# design.net
KiCad netlist of a schematic drawn in Altium Designer
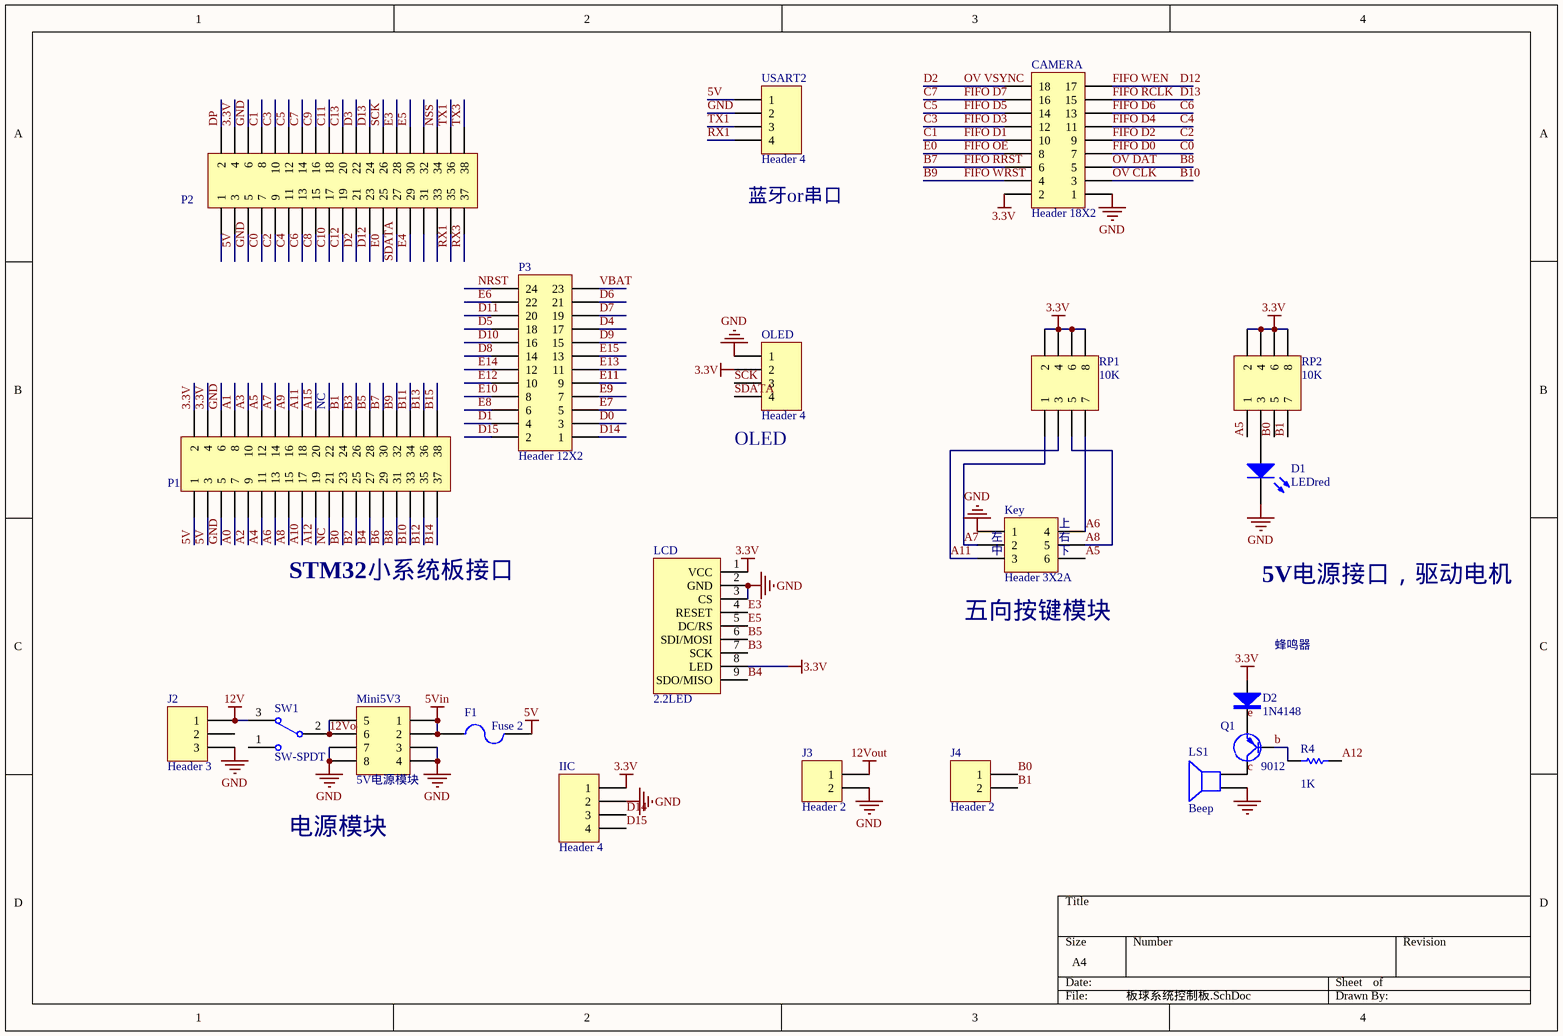
[diagram p0: 板球系统控制板.SchDoc]

(export (version "E")
  (design (tool "Eeschema 10.0.6"))
  (components
    (comp (ref "CAMERA")
      (value "Header 18X2")
      (footprint "HDR2X9H")
      (description "Header, 9-Pin, Dual row")
      (fields (field (name "PUBLISHER") "Altium Limited"))
      (libsource (lib "Miscellaneous Connectors") (part "Header 9X2"))
    )
    (comp (ref "D1")
      (value "LEDred")
      (footprint "0805_LED_S4")
      (description "Typical INFRARED GaAs LED")
      (fields (field (name "PUBLISHER") "Altium Limited"))
      (libsource (lib "Miscellaneous Devices") (part "LED0"))
    )
    (comp (ref "D2")
      (value "1N4148")
      (footprint "SOD-123")
      (description "Diode")
      (libsource (lib "*") (part "1N4148"))
    )
    (comp (ref "F1")
      (value "Fuse 2")
      (footprint "0805")
      (description "Fuse")
      (fields (field (name "PUBLISHER") "Altium Limited"))
      (libsource (lib "Miscellaneous Devices") (part "Fuse 2"))
    )
    (comp (ref "IIC")
      (value "Header 4")
      (footprint "sip4")
      (description "Header, 4-Pin")
      (fields (field (name "PUBLISHER") "Altium Limited"))
      (libsource (lib "Miscellaneous Connectors") (part "Header 4"))
    )
    (comp (ref "J2")
      (value "Header 3")
      (footprint "Power")
      (description "Header, 3-Pin")
      (fields (field (name "PUBLISHER") "Altium Limited"))
      (libsource (lib "Miscellaneous Connectors") (part "Header 3"))
    )
    (comp (ref "J3")
      (value "Header 2")
      (footprint "HDR1X2")
      (description "Header, 2-Pin")
      (fields (field (name "PUBLISHER") "Altium Limited"))
      (libsource (lib "Miscellaneous Connectors") (part "Header 2"))
    )
    (comp (ref "J4")
      (value "Header 2")
      (footprint "HDR1X2")
      (description "Header, 2-Pin")
      (fields (field (name "PUBLISHER") "Altium Limited"))
      (libsource (lib "Miscellaneous Connectors") (part "Header 2"))
    )
    (comp (ref "Key")
      (value "Header 3X2A")
      (footprint "Key5D")
      (description "Header, 3-Pin, Dual row")
      (fields (field (name "PUBLISHER") "Altium Limited"))
      (libsource (lib "Miscellaneous Connectors") (part "Header 3X2A"))
    )
    (comp (ref "LCD")
      (value "2.2LED")
      (footprint "2.2LCD")
      (libsource (lib "MyselfSchLibSCH") (part "2.2LED"))
    )
    (comp (ref "LS1") (value "Beep") (footprint "BUFFER-12") (libsource (lib "*") (part "SPEAKER")))
    (comp (ref "Mini5V3")
      (value "5V电源模块")
      (footprint "Mini5Vpower")
      (description "Header, 4-Pin, Dual row")
      (fields (field (name "PUBLISHER") "Altium Limited"))
      (libsource (lib "Miscellaneous Connectors") (part "Header 4X2A"))
    )
    (comp (ref "OLED")
      (value "Header 4")
      (footprint "sip4")
      (description "Header, 4-Pin")
      (fields (field (name "PUBLISHER") "Altium Limited"))
      (libsource (lib "") (part "Header 4_1"))
    )
    (comp (ref "P1")
      (value "Header 19X2")
      (footprint "HDR2X19")
      (description "Header, 19-Pin, Dual row")
      (fields (field (name "PUBLISHER") "Altium Limited"))
      (libsource (lib "Miscellaneous Connectors") (part "Header 19X2"))
    )
    (comp (ref "P2")
      (value "Header 19X2")
      (footprint "HDR2X19")
      (description "Header, 19-Pin, Dual row")
      (fields (field (name "PUBLISHER") "Altium Limited"))
      (libsource (lib "Miscellaneous Connectors") (part "Header 19X2"))
    )
    (comp (ref "P3")
      (value "Header 12X2")
      (footprint "HDR2X12")
      (description "Header, 12-Pin, Dual row")
      (fields (field (name "PUBLISHER") "Altium Limited"))
      (libsource (lib "Miscellaneous Connectors") (part "Header 12X2"))
    )
    (comp (ref "Q1") (value "9012") (footprint "SOT23") (libsource (lib "MyselfSchLibSCH") (part "9012")))
    (comp (ref "R4")
      (value "1K")
      (footprint "0805_R")
      (description "Resistor")
      (fields (field (name "Comment") "Res1") (field (name "PUBLISHER") "Altium Limited"))
      (libsource (lib "Miscellaneous Devices") (part "Res1"))
    )
    (comp (ref "RP1")
      (value "10K")
      (footprint "R0603_8P4R")
      (description "Header, 4-Pin, Dual row")
      (fields (field (name "PUBLISHER") "Altium Limited"))
      (libsource (lib "Miscellaneous Connectors") (part "Header 4X2"))
    )
    (comp (ref "RP2")
      (value "10K")
      (footprint "R0603_8P4R")
      (description "Header, 4-Pin, Dual row")
      (fields (field (name "PUBLISHER") "Altium Limited"))
      (libsource (lib "Miscellaneous Connectors") (part "Header 4X2"))
    )
    (comp (ref "SW1")
      (value "SW-SPDT")
      (footprint "switch2")
      (description "SPDT Subminiature Toggle Switch, Right Angle Mounting, Vertical Actuation")
      (fields (field (name "PUBLISHER") "Altium Limited"))
      (libsource (lib "Miscellaneous Devices") (part "SW-SPDT"))
    )
    (comp (ref "USART2")
      (value "Header 4")
      (footprint "HDR1X4")
      (description "Header, 4-Pin")
      (fields (field (name "PUBLISHER") "Altium Limited"))
      (libsource (lib "") (part "Header 4_1"))
    )
  )
  (nets
    (net (code "1") (name "/A0") (class "Default")
      (node (ref "P1") (pin "7") (pinfunction "7_7") (pintype "passive"))
    )
    (net (code "2") (name "/A1") (class "Default")
      (node (ref "P1") (pin "8") (pinfunction "8_8") (pintype "passive"))
    )
    (net (code "3") (name "/A2") (class "Default")
      (node (ref "P1") (pin "9") (pinfunction "9_9") (pintype "passive"))
    )
    (net (code "4") (name "/A3") (class "Default")
      (node (ref "P1") (pin "10") (pinfunction "10_10") (pintype "passive"))
    )
    (net (code "5") (name "/A4") (class "Default")
      (node (ref "P1") (pin "11") (pinfunction "11_11") (pintype "passive"))
    )
    (net (code "6") (name "/A5") (class "Default")
      (node (ref "Key") (pin "6") (pinfunction "6_6") (pintype "passive"))
      (node (ref "P1") (pin "12") (pinfunction "12_12") (pintype "passive"))
      (node (ref "RP2") (pin "1") (pinfunction "1_1") (pintype "passive"))
    )
    (net (code "7") (name "/A6") (class "Default")
      (node (ref "Key") (pin "4") (pinfunction "4_4") (pintype "passive"))
      (node (ref "P1") (pin "13") (pinfunction "13_13") (pintype "passive"))
      (node (ref "RP1") (pin "7") (pinfunction "7_7") (pintype "passive"))
    )
    (net (code "8") (name "/A7") (class "Default")
      (node (ref "Key") (pin "2") (pinfunction "2_2") (pintype "passive"))
      (node (ref "P1") (pin "14") (pinfunction "14_14") (pintype "passive"))
      (node (ref "RP1") (pin "1") (pinfunction "1_1") (pintype "passive"))
    )
    (net (code "9") (name "/A8") (class "Default")
      (node (ref "Key") (pin "5") (pinfunction "5_5") (pintype "passive"))
      (node (ref "P1") (pin "15") (pinfunction "15_15") (pintype "passive"))
      (node (ref "RP1") (pin "5") (pinfunction "5_5") (pintype "passive"))
    )
    (net (code "10") (name "/A9") (class "Default")
      (node (ref "P1") (pin "16") (pinfunction "16_16") (pintype "passive"))
    )
    (net (code "11") (name "/A10") (class "Default")
      (node (ref "P1") (pin "17") (pinfunction "17_17") (pintype "passive"))
    )
    (net (code "12") (name "/A11") (class "Default")
      (node (ref "Key") (pin "3") (pinfunction "3_3") (pintype "passive"))
      (node (ref "P1") (pin "18") (pinfunction "18_18") (pintype "passive"))
      (node (ref "RP1") (pin "3") (pinfunction "3_3") (pintype "passive"))
    )
    (net (code "13") (name "/A12") (class "Default")
      (node (ref "P1") (pin "19") (pinfunction "19_19") (pintype "passive"))
      (node (ref "R4") (pin "2") (pinfunction "2_2") (pintype "passive"))
    )
    (net (code "14") (name "/A15") (class "Default")
      (node (ref "P1") (pin "20") (pinfunction "20_20") (pintype "passive"))
    )
    (net (code "15") (name "/B0") (class "Default")
      (node (ref "J4") (pin "1") (pinfunction "1_1") (pintype "passive"))
      (node (ref "P1") (pin "23") (pinfunction "23_23") (pintype "passive"))
      (node (ref "RP2") (pin "5") (pinfunction "5_5") (pintype "passive"))
    )
    (net (code "16") (name "/B1") (class "Default")
      (node (ref "J4") (pin "2") (pinfunction "2_2") (pintype "passive"))
      (node (ref "P1") (pin "24") (pinfunction "24_24") (pintype "passive"))
      (node (ref "RP2") (pin "7") (pinfunction "7_7") (pintype "passive"))
    )
    (net (code "17") (name "/B2") (class "Default")
      (node (ref "P1") (pin "25") (pinfunction "25_25") (pintype "passive"))
    )
    (net (code "18") (name "/B3") (class "Default")
      (node (ref "LCD") (pin "7") (pinfunction "SCK_7") (pintype "passive"))
      (node (ref "P1") (pin "26") (pinfunction "26_26") (pintype "passive"))
    )
    (net (code "19") (name "/B4") (class "Default")
      (node (ref "LCD") (pin "9") (pinfunction "SDO/MISO_9") (pintype "passive"))
      (node (ref "P1") (pin "27") (pinfunction "27_27") (pintype "passive"))
    )
    (net (code "20") (name "/B5") (class "Default")
      (node (ref "LCD") (pin "6") (pinfunction "SDI/MOSI_6") (pintype "passive"))
      (node (ref "P1") (pin "28") (pinfunction "28_28") (pintype "passive"))
    )
    (net (code "21") (name "/B6") (class "Default")
      (node (ref "P1") (pin "29") (pinfunction "29_29") (pintype "passive"))
    )
    (net (code "22") (name "/B7") (class "Default")
      (node (ref "CAMERA") (pin "6") (pinfunction "6_6") (pintype "passive"))
      (node (ref "P1") (pin "30") (pinfunction "30_30") (pintype "passive"))
    )
    (net (code "23") (name "/B8") (class "Default")
      (node (ref "CAMERA") (pin "5") (pinfunction "5_5") (pintype "passive"))
      (node (ref "P1") (pin "31") (pinfunction "31_31") (pintype "passive"))
    )
    (net (code "24") (name "/B9") (class "Default")
      (node (ref "CAMERA") (pin "4") (pinfunction "4_4") (pintype "passive"))
      (node (ref "P1") (pin "32") (pinfunction "32_32") (pintype "passive"))
    )
    (net (code "25") (name "/B10") (class "Default")
      (node (ref "CAMERA") (pin "3") (pinfunction "3_3") (pintype "passive"))
      (node (ref "P1") (pin "33") (pinfunction "33_33") (pintype "passive"))
    )
    (net (code "26") (name "/B11") (class "Default")
      (node (ref "P1") (pin "34") (pinfunction "34_34") (pintype "passive"))
    )
    (net (code "27") (name "/B12") (class "Default")
      (node (ref "P1") (pin "35") (pinfunction "35_35") (pintype "passive"))
    )
    (net (code "28") (name "/B13") (class "Default")
      (node (ref "P1") (pin "36") (pinfunction "36_36") (pintype "passive"))
    )
    (net (code "29") (name "/B14") (class "Default")
      (node (ref "P1") (pin "37") (pinfunction "37_37") (pintype "passive"))
    )
    (net (code "30") (name "/B15") (class "Default")
      (node (ref "P1") (pin "38") (pinfunction "38_38") (pintype "passive"))
    )
    (net (code "31") (name "/C0") (class "Default")
      (node (ref "CAMERA") (pin "7") (pinfunction "7_7") (pintype "passive"))
      (node (ref "P2") (pin "7") (pinfunction "7_7") (pintype "passive"))
    )
    (net (code "32") (name "/C1") (class "Default")
      (node (ref "CAMERA") (pin "10") (pinfunction "10_10") (pintype "passive"))
      (node (ref "P2") (pin "8") (pinfunction "8_8") (pintype "passive"))
    )
    (net (code "33") (name "/C2") (class "Default")
      (node (ref "CAMERA") (pin "9") (pinfunction "9_9") (pintype "passive"))
      (node (ref "P2") (pin "9") (pinfunction "9_9") (pintype "passive"))
    )
    (net (code "34") (name "/C3") (class "Default")
      (node (ref "CAMERA") (pin "12") (pinfunction "12_12") (pintype "passive"))
      (node (ref "P2") (pin "10") (pinfunction "10_10") (pintype "passive"))
    )
    (net (code "35") (name "/C4") (class "Default")
      (node (ref "CAMERA") (pin "11") (pinfunction "11_11") (pintype "passive"))
      (node (ref "P2") (pin "11") (pinfunction "11_11") (pintype "passive"))
    )
    (net (code "36") (name "/C5") (class "Default")
      (node (ref "CAMERA") (pin "14") (pinfunction "14_14") (pintype "passive"))
      (node (ref "P2") (pin "12") (pinfunction "12_12") (pintype "passive"))
    )
    (net (code "37") (name "/C6") (class "Default")
      (node (ref "CAMERA") (pin "13") (pinfunction "13_13") (pintype "passive"))
      (node (ref "P2") (pin "13") (pinfunction "13_13") (pintype "passive"))
    )
    (net (code "38") (name "/C7") (class "Default")
      (node (ref "CAMERA") (pin "16") (pinfunction "16_16") (pintype "passive"))
      (node (ref "P2") (pin "14") (pinfunction "14_14") (pintype "passive"))
    )
    (net (code "39") (name "/C8") (class "Default")
      (node (ref "P2") (pin "15") (pinfunction "15_15") (pintype "passive"))
    )
    (net (code "40") (name "/C9") (class "Default")
      (node (ref "P2") (pin "16") (pinfunction "16_16") (pintype "passive"))
    )
    (net (code "41") (name "/C10") (class "Default")
      (node (ref "P2") (pin "17") (pinfunction "17_17") (pintype "passive"))
    )
    (net (code "42") (name "/C11") (class "Default")
      (node (ref "P2") (pin "18") (pinfunction "18_18") (pintype "passive"))
    )
    (net (code "43") (name "/C12") (class "Default")
      (node (ref "P2") (pin "19") (pinfunction "19_19") (pintype "passive"))
    )
    (net (code "44") (name "/C13") (class "Default")
      (node (ref "P2") (pin "20") (pinfunction "20_20") (pintype "passive"))
    )
    (net (code "45") (name "/D0") (class "Default")
      (node (ref "P3") (pin "3") (pinfunction "3_3") (pintype "passive"))
    )
    (net (code "46") (name "/D1") (class "Default")
      (node (ref "P3") (pin "4") (pinfunction "4_4") (pintype "passive"))
    )
    (net (code "47") (name "/D2") (class "Default")
      (node (ref "CAMERA") (pin "18") (pinfunction "18_18") (pintype "passive"))
      (node (ref "P2") (pin "21") (pinfunction "21_21") (pintype "passive"))
    )
    (net (code "48") (name "/D3") (class "Default")
      (node (ref "P2") (pin "22") (pinfunction "22_22") (pintype "passive"))
    )
    (net (code "49") (name "/D4") (class "Default")
      (node (ref "P3") (pin "17") (pinfunction "17_17") (pintype "passive"))
    )
    (net (code "50") (name "/D5") (class "Default")
      (node (ref "P3") (pin "18") (pinfunction "18_18") (pintype "passive"))
    )
    (net (code "51") (name "/D6") (class "Default")
      (node (ref "P3") (pin "21") (pinfunction "21_21") (pintype "passive"))
    )
    (net (code "52") (name "/D7") (class "Default")
      (node (ref "P3") (pin "19") (pinfunction "19_19") (pintype "passive"))
    )
    (net (code "53") (name "/D8") (class "Default")
      (node (ref "P3") (pin "14") (pinfunction "14_14") (pintype "passive"))
    )
    (net (code "54") (name "/D9") (class "Default")
      (node (ref "P3") (pin "15") (pinfunction "15_15") (pintype "passive"))
    )
    (net (code "55") (name "/D10") (class "Default")
      (node (ref "P3") (pin "16") (pinfunction "16_16") (pintype "passive"))
    )
    (net (code "56") (name "/D11") (class "Default")
      (node (ref "P3") (pin "20") (pinfunction "20_20") (pintype "passive"))
    )
    (net (code "57") (name "/D12") (class "Default")
      (node (ref "CAMERA") (pin "17") (pinfunction "17_17") (pintype "passive"))
      (node (ref "P2") (pin "23") (pinfunction "23_23") (pintype "passive"))
    )
    (net (code "58") (name "/D13") (class "Default")
      (node (ref "CAMERA") (pin "15") (pinfunction "15_15") (pintype "passive"))
      (node (ref "P2") (pin "24") (pinfunction "24_24") (pintype "passive"))
    )
    (net (code "59") (name "/D14") (class "Default")
      (node (ref "IIC") (pin "3") (pinfunction "3_3") (pintype "passive"))
      (node (ref "P3") (pin "1") (pinfunction "1_1") (pintype "passive"))
    )
    (net (code "60") (name "/D15") (class "Default")
      (node (ref "IIC") (pin "4") (pinfunction "4_4") (pintype "passive"))
      (node (ref "P3") (pin "2") (pinfunction "2_2") (pintype "passive"))
    )
    (net (code "61") (name "/DP") (class "Default")
      (node (ref "P2") (pin "2") (pinfunction "2_2") (pintype "passive"))
    )
    (net (code "62") (name "/E0") (class "Default")
      (node (ref "CAMERA") (pin "8") (pinfunction "8_8") (pintype "passive"))
      (node (ref "P2") (pin "25") (pinfunction "25_25") (pintype "passive"))
    )
    (net (code "63") (name "/E3") (class "Default")
      (node (ref "LCD") (pin "4") (pinfunction "RESET_4") (pintype "passive"))
      (node (ref "P2") (pin "28") (pinfunction "28_28") (pintype "passive"))
    )
    (net (code "64") (name "/E4") (class "Default")
      (node (ref "P2") (pin "29") (pinfunction "29_29") (pintype "passive"))
    )
    (net (code "65") (name "/E5") (class "Default")
      (node (ref "LCD") (pin "5") (pinfunction "DC/RS_5") (pintype "passive"))
      (node (ref "P2") (pin "30") (pinfunction "30_30") (pintype "passive"))
    )
    (net (code "66") (name "/E6") (class "Default")
      (node (ref "P3") (pin "22") (pinfunction "22_22") (pintype "passive"))
    )
    (net (code "67") (name "/E7") (class "Default")
      (node (ref "P3") (pin "5") (pinfunction "5_5") (pintype "passive"))
    )
    (net (code "68") (name "/E8") (class "Default")
      (node (ref "P3") (pin "6") (pinfunction "6_6") (pintype "passive"))
    )
    (net (code "69") (name "/E9") (class "Default")
      (node (ref "P3") (pin "7") (pinfunction "7_7") (pintype "passive"))
    )
    (net (code "70") (name "/E10") (class "Default")
      (node (ref "P3") (pin "8") (pinfunction "8_8") (pintype "passive"))
    )
    (net (code "71") (name "/E11") (class "Default")
      (node (ref "P3") (pin "9") (pinfunction "9_9") (pintype "passive"))
    )
    (net (code "72") (name "/E12") (class "Default")
      (node (ref "P3") (pin "10") (pinfunction "10_10") (pintype "passive"))
    )
    (net (code "73") (name "/E13") (class "Default")
      (node (ref "P3") (pin "11") (pinfunction "11_11") (pintype "passive"))
    )
    (net (code "74") (name "/E14") (class "Default")
      (node (ref "P3") (pin "12") (pinfunction "12_12") (pintype "passive"))
    )
    (net (code "75") (name "/E15") (class "Default")
      (node (ref "P3") (pin "13") (pinfunction "13_13") (pintype "passive"))
    )
    (net (code "76") (name "/NC") (class "Default")
      (node (ref "P1") (pin "21") (pinfunction "21_21") (pintype "passive"))
    )
    (net (code "77") (name "/NRST") (class "Default")
      (node (ref "P3") (pin "24") (pinfunction "24_24") (pintype "passive"))
    )
    (net (code "78") (name "/NSS") (class "Default")
      (node (ref "P2") (pin "34") (pinfunction "34_34") (pintype "passive"))
    )
    (net (code "79") (name "/RX1") (class "Default")
      (node (ref "P2") (pin "35") (pinfunction "35_35") (pintype "passive"))
      (node (ref "USART2") (pin "4") (pinfunction "4_4") (pintype "passive"))
    )
    (net (code "80") (name "/RX3") (class "Default")
      (node (ref "P2") (pin "37") (pinfunction "37_37") (pintype "passive"))
    )
    (net (code "81") (name "/SCK") (class "Default")
      (node (ref "OLED") (pin "3") (pinfunction "3_3") (pintype "passive"))
      (node (ref "P2") (pin "26") (pinfunction "26_26") (pintype "passive"))
    )
    (net (code "82") (name "/SDATA") (class "Default")
      (node (ref "OLED") (pin "4") (pinfunction "4_4") (pintype "passive"))
      (node (ref "P2") (pin "27") (pinfunction "27_27") (pintype "passive"))
    )
    (net (code "83") (name "/TX1") (class "Default")
      (node (ref "P2") (pin "36") (pinfunction "36_36") (pintype "passive"))
      (node (ref "USART2") (pin "3") (pinfunction "3_3") (pintype "passive"))
    )
    (net (code "84") (name "/TX3") (class "Default")
      (node (ref "P2") (pin "38") (pinfunction "38_38") (pintype "passive"))
    )
    (net (code "85") (name "/VBAT") (class "Default")
      (node (ref "P3") (pin "23") (pinfunction "23_23") (pintype "passive"))
    )
    (net (code "86") (name "/b") (class "Default")
      (node (ref "Q1") (pin "1") (pinfunction "B_1") (pintype "passive"))
      (node (ref "R4") (pin "1") (pinfunction "1_1") (pintype "passive"))
    )
    (net (code "87") (name "/c") (class "Default")
      (node (ref "LS1") (pin "1") (pinfunction "1_1") (pintype "passive"))
      (node (ref "Q1") (pin "3") (pinfunction "C_3") (pintype "passive"))
    )
    (net (code "88") (name "/e") (class "Default")
      (node (ref "D2") (pin "2") (pinfunction "K_2") (pintype "passive"))
      (node (ref "Q1") (pin "2") (pinfunction "E_2") (pintype "passive"))
    )
    (net (code "89") (name "3.3V") (class "Default")
      (node (ref "CAMERA") (pin "2") (pinfunction "2_2") (pintype "passive"))
      (node (ref "D2") (pin "1") (pinfunction "A_1") (pintype "passive"))
      (node (ref "IIC") (pin "1") (pinfunction "1_1") (pintype "passive"))
      (node (ref "LCD") (pin "1") (pinfunction "VCC_1") (pintype "passive"))
      (node (ref "LCD") (pin "8") (pinfunction "LED_8") (pintype "passive"))
      (node (ref "OLED") (pin "2") (pinfunction "2_2") (pintype "passive"))
      (node (ref "P1") (pin "2") (pinfunction "2_2") (pintype "passive"))
      (node (ref "P1") (pin "4") (pinfunction "4_4") (pintype "passive"))
      (node (ref "P2") (pin "4") (pinfunction "4_4") (pintype "passive"))
      (node (ref "RP1") (pin "2") (pinfunction "2_2") (pintype "passive"))
      (node (ref "RP1") (pin "4") (pinfunction "4_4") (pintype "passive"))
      (node (ref "RP1") (pin "6") (pinfunction "6_6") (pintype "passive"))
      (node (ref "RP1") (pin "8") (pinfunction "8_8") (pintype "passive"))
      (node (ref "RP2") (pin "2") (pinfunction "2_2") (pintype "passive"))
      (node (ref "RP2") (pin "4") (pinfunction "4_4") (pintype "passive"))
      (node (ref "RP2") (pin "6") (pinfunction "6_6") (pintype "passive"))
      (node (ref "RP2") (pin "8") (pinfunction "8_8") (pintype "passive"))
    )
    (net (code "90") (name "5V") (class "Default")
      (node (ref "F1") (pin "2") (pinfunction "2_2") (pintype "passive"))
      (node (ref "P1") (pin "1") (pinfunction "1_1") (pintype "passive"))
      (node (ref "P1") (pin "3") (pinfunction "3_3") (pintype "passive"))
      (node (ref "P2") (pin "3") (pinfunction "3_3") (pintype "passive"))
      (node (ref "USART2") (pin "1") (pinfunction "1_1") (pintype "passive"))
    )
    (net (code "91") (name "5Vin") (class "Default")
      (node (ref "F1") (pin "1") (pinfunction "1_1") (pintype "passive"))
      (node (ref "Mini5V3") (pin "1") (pinfunction "1_1") (pintype "passive"))
      (node (ref "Mini5V3") (pin "2") (pinfunction "2_2") (pintype "passive"))
    )
    (net (code "92") (name "12V") (class "Default")
      (node (ref "J2") (pin "1") (pinfunction "1_1") (pintype "passive"))
      (node (ref "SW1") (pin "3") (pinfunction "3_3") (pintype "passive"))
    )
    (net (code "93") (name "12Vout") (class "Default")
      (node (ref "J3") (pin "1") (pinfunction "1_1") (pintype "passive"))
      (node (ref "Mini5V3") (pin "5") (pinfunction "5_5") (pintype "passive"))
      (node (ref "Mini5V3") (pin "6") (pinfunction "6_6") (pintype "passive"))
      (node (ref "SW1") (pin "2") (pinfunction "2_2") (pintype "passive"))
    )
    (net (code "94") (name "GND") (class "Default")
      (node (ref "CAMERA") (pin "1") (pinfunction "1_1") (pintype "passive"))
      (node (ref "D1") (pin "2") (pinfunction "K_2") (pintype "passive"))
      (node (ref "IIC") (pin "2") (pinfunction "2_2") (pintype "passive"))
      (node (ref "J2") (pin "3") (pinfunction "3_3") (pintype "passive"))
      (node (ref "J3") (pin "2") (pinfunction "2_2") (pintype "passive"))
      (node (ref "Key") (pin "1") (pinfunction "1_1") (pintype "passive"))
      (node (ref "LCD") (pin "2") (pinfunction "GND_2") (pintype "passive"))
      (node (ref "LCD") (pin "3") (pinfunction "CS_3") (pintype "passive"))
      (node (ref "LS1") (pin "2") (pinfunction "2_2") (pintype "passive"))
      (node (ref "Mini5V3") (pin "3") (pinfunction "3_3") (pintype "passive"))
      (node (ref "Mini5V3") (pin "4") (pinfunction "4_4") (pintype "passive"))
      (node (ref "Mini5V3") (pin "7") (pinfunction "7_7") (pintype "passive"))
      (node (ref "Mini5V3") (pin "8") (pinfunction "8_8") (pintype "passive"))
      (node (ref "OLED") (pin "1") (pinfunction "1_1") (pintype "passive"))
      (node (ref "P1") (pin "5") (pinfunction "5_5") (pintype "passive"))
      (node (ref "P1") (pin "6") (pinfunction "6_6") (pintype "passive"))
      (node (ref "P2") (pin "5") (pinfunction "5_5") (pintype "passive"))
      (node (ref "P2") (pin "6") (pinfunction "6_6") (pintype "passive"))
      (node (ref "USART2") (pin "2") (pinfunction "2_2") (pintype "passive"))
    )
    (net (code "95") (name "Net-(D1-A)") (class "Default")
      (node (ref "D1") (pin "1") (pinfunction "A_1") (pintype "passive"))
      (node (ref "RP2") (pin "3") (pinfunction "3_3") (pintype "passive"))
    )
    (net (code "96") (name "unconnected-(J2-Pad2)") (class "Default")
      (node (ref "J2") (pin "2") (pinfunction "2_2") (pintype "passive"))
    )
    (net (code "97") (name "unconnected-(P1-Pad22)") (class "Default")
      (node (ref "P1") (pin "22") (pinfunction "22_22") (pintype "passive"))
    )
    (net (code "98") (name "unconnected-(P2-Pad1)") (class "Default")
      (node (ref "P2") (pin "1") (pinfunction "1_1") (pintype "passive"))
    )
    (net (code "99") (name "unconnected-(P2-Pad31)") (class "Default")
      (node (ref "P2") (pin "31") (pinfunction "31_31") (pintype "passive"))
    )
    (net (code "100") (name "unconnected-(P2-Pad32)") (class "Default")
      (node (ref "P2") (pin "32") (pinfunction "32_32") (pintype "passive"))
    )
    (net (code "101") (name "unconnected-(P2-Pad33)") (class "Default")
      (node (ref "P2") (pin "33") (pinfunction "33_33") (pintype "passive"))
    )
    (net (code "102") (name "unconnected-(SW1-Pad1)") (class "Default")
      (node (ref "SW1") (pin "1") (pinfunction "1_1") (pintype "passive"))
    )
  )
)
